# FPGA_14_15.net
KiCad netlist of a schematic drawn in Altium Designer
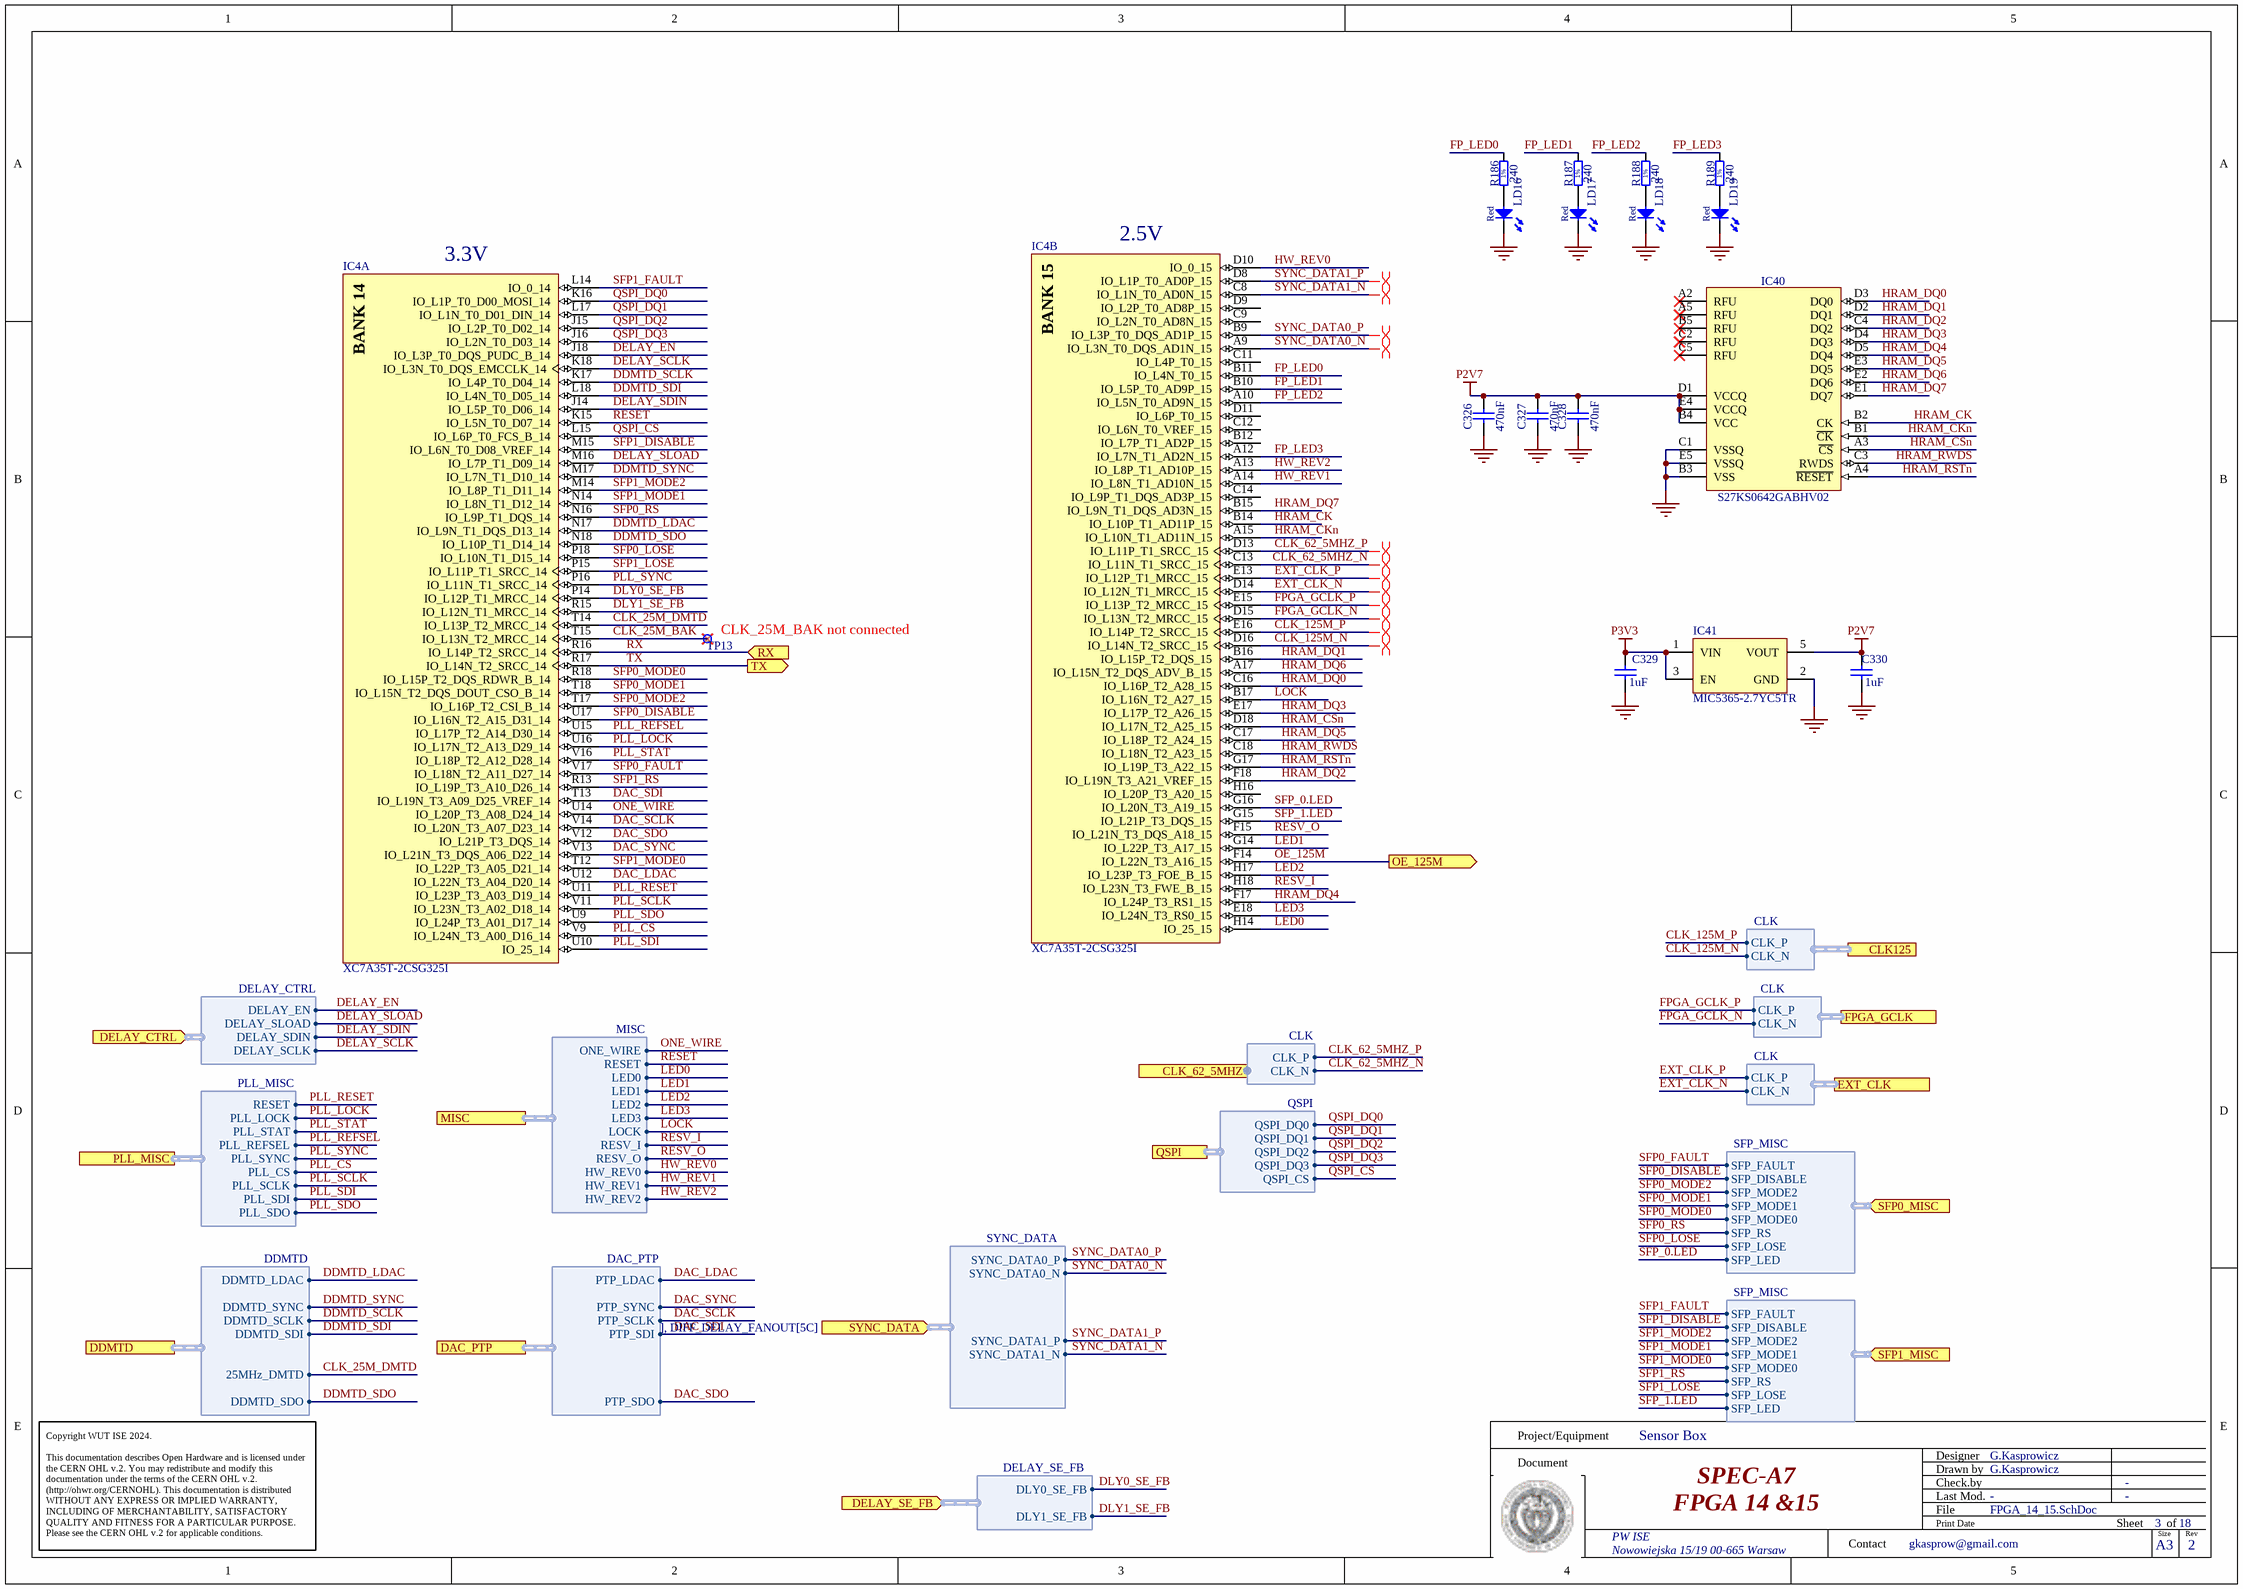
[diagram p0: FPGA_14_15.SchDoc]

(export (version "E")
  (design (tool "Eeschema 10.0.6"))
  (components
    (comp (ref "C326")
      (value "470nF")
      (footprint "CAPC0603X33N")
      (description "Non-polarised capacitor")
      (fields
        (field (name "PART NUMBER") "CC0201_470NF_4V_20%_X5R")
        (field (name "VOLTAGE") "4V")
        (field (name "AUTHOR") "CERN DEM JLC")
      )
      (libsource (lib "Capacitors") (part "Capacitor - non polarized"))
    )
    (comp (ref "C327")
      (value "470nF")
      (footprint "CAPC0603X33N")
      (description "Non-polarised capacitor")
      (fields
        (field (name "PART NUMBER") "CC0201_470NF_4V_20%_X5R")
        (field (name "VOLTAGE") "4V")
        (field (name "AUTHOR") "CERN DEM JLC")
      )
      (libsource (lib "Capacitors") (part "Capacitor - non polarized"))
    )
    (comp (ref "C328")
      (value "470nF")
      (footprint "CAPC0603X33N")
      (description "Non-polarised capacitor")
      (fields
        (field (name "PART NUMBER") "CC0201_470NF_4V_20%_X5R")
        (field (name "VOLTAGE") "4V")
        (field (name "AUTHOR") "CERN DEM JLC")
      )
      (libsource (lib "Capacitors") (part "Capacitor - non polarized"))
    )
    (comp (ref "C329")
      (value "1uF")
      (footprint "CAPC1005X55N")
      (description "Non-polarised capacitor")
      (fields
        (field (name "PART NUMBER") "CC0402_1UF_16V_10%_X5R")
        (field (name "VOLTAGE") "16V")
        (field (name "AUTHOR") "CERN DEM JLC")
      )
      (libsource (lib "Capacitors") (part "Capacitor - non polarized"))
    )
    (comp (ref "C330")
      (value "1uF")
      (footprint "CAPC1005X55N")
      (description "Non-polarised capacitor")
      (fields
        (field (name "PART NUMBER") "CC0402_1UF_16V_10%_X5R")
        (field (name "VOLTAGE") "16V")
        (field (name "AUTHOR") "CERN DEM JLC")
      )
      (libsource (lib "Capacitors") (part "Capacitor - non polarized"))
    )
    (comp (ref "IC4")
      (value "XC7A35T-2CSG325I")
      (footprint "CSG325")
      (description "Artix-7 FPGA, 150 User I/Os, 4 GTP, 324-Ball BGA, Speed Grade 2, Industrial Grade, Pb-Free")
      (fields (field (name "MANUFACTURER") "Xilinx"))
      (libsource (lib "Altium Content Vault") (part "XLNX-XC7A35T-CSG325"))
    )
    (comp (ref "IC40")
      (value "S27KS0642GABHV02")
      (footprint "BGA24C100P5X5_600X800X100")
      (description "1.8V, Multiple I/O Serial NOR Flash Memory, with Reset# & Hold# Pins")
      (fields (field (name "MANUFACTURER") "INFINEON") (field (name "AUTHOR") "CERN DEM HF"))
      (libsource (lib "ICs And Semiconductors") (part "S27KS0642GABHV02"))
    )
    (comp (ref "IC41")
      (value "MIC5365-2.7YC5TR")
      (footprint "SOT65P210X110-5N")
      (libsource (lib "MGlib") (part "MIC5365-2.7YC5TR"))
    )
    (comp (ref "LD16")
      (value "Red")
      (footprint "LED_AVAGO_HSMC-C120")
      (description "LED Red 1C 2A")
      (fields
        (field (name "PART NUMBER") "LED_AVAGO_HSMC-C120")
        (field (name "MANUFACTURER") "AVAGO TECHNOLOGIES")
        (field (name "AUTHOR") "CERN DEM JMW")
      )
      (libsource (lib "ICs And Semiconductors") (part "LED Red 1C 2A"))
    )
    (comp (ref "LD17")
      (value "Red")
      (footprint "LED_AVAGO_HSMC-C120")
      (description "LED Red 1C 2A")
      (fields
        (field (name "PART NUMBER") "LED_AVAGO_HSMC-C120")
        (field (name "MANUFACTURER") "AVAGO TECHNOLOGIES")
        (field (name "AUTHOR") "CERN DEM JMW")
      )
      (libsource (lib "ICs And Semiconductors") (part "LED Red 1C 2A"))
    )
    (comp (ref "LD18")
      (value "Red")
      (footprint "LED_AVAGO_HSMC-C120")
      (description "LED Red 1C 2A")
      (fields
        (field (name "PART NUMBER") "LED_AVAGO_HSMC-C120")
        (field (name "MANUFACTURER") "AVAGO TECHNOLOGIES")
        (field (name "AUTHOR") "CERN DEM JMW")
      )
      (libsource (lib "ICs And Semiconductors") (part "LED Red 1C 2A"))
    )
    (comp (ref "LD19")
      (value "Red")
      (footprint "LED_AVAGO_HSMC-C120")
      (description "LED Red 1C 2A")
      (fields
        (field (name "PART NUMBER") "LED_AVAGO_HSMC-C120")
        (field (name "MANUFACTURER") "AVAGO TECHNOLOGIES")
        (field (name "AUTHOR") "CERN DEM JMW")
      )
      (libsource (lib "ICs And Semiconductors") (part "LED Red 1C 2A"))
    )
    (comp (ref "R186")
      (value "240")
      (footprint "RESC1005X40N")
      (description "Resistor - 1%")
      (fields
        (field (name "PART NUMBER") "R0402_240R_1%_0.0625W_100PPM")
        (field (name "POWER") "0.0625W")
        (field (name "AUTHOR") "CERN DEM JLC")
      )
      (libsource (lib "Resistors") (part "Resistor - 1%"))
    )
    (comp (ref "R187")
      (value "240")
      (footprint "RESC1005X40N")
      (description "Resistor - 1%")
      (fields
        (field (name "PART NUMBER") "R0402_240R_1%_0.0625W_100PPM")
        (field (name "POWER") "0.0625W")
        (field (name "AUTHOR") "CERN DEM JLC")
      )
      (libsource (lib "Resistors") (part "Resistor - 1%"))
    )
    (comp (ref "R188")
      (value "240")
      (footprint "RESC1005X40N")
      (description "Resistor - 1%")
      (fields
        (field (name "PART NUMBER") "R0402_240R_1%_0.0625W_100PPM")
        (field (name "POWER") "0.0625W")
        (field (name "AUTHOR") "CERN DEM JLC")
      )
      (libsource (lib "Resistors") (part "Resistor - 1%"))
    )
    (comp (ref "R189")
      (value "240")
      (footprint "RESC1005X40N")
      (description "Resistor - 1%")
      (fields
        (field (name "PART NUMBER") "R0402_240R_1%_0.0625W_100PPM")
        (field (name "POWER") "0.0625W")
        (field (name "AUTHOR") "CERN DEM JLC")
      )
      (libsource (lib "Resistors") (part "Resistor - 1%"))
    )
    (comp (ref "TP13")
      (value "Test Point")
      (footprint "TPS060")
      (fields (field (name "PART NUMBER") "SMD_PAD_0.6X0.6MM") (field (name "AUTHOR") "CERN DEM HF"))
      (libsource (lib "Eletro-mechanical") (part "Test Point"))
    )
  )
  (nets
    (net (code "11") (name "/CLK_25M_BAK") (class "Default")
      (node (ref "IC4") (pin "T15") (pinfunction "IO_L13N_T2_MRCC_14_T15") (pintype "bidirectional"))
      (node (ref "TP13") (pin "1") (pinfunction "1_1") (pintype "bidirectional"))
    )
    (net (code "12") (name "/CLK_25M_DMTD") (class "Default")
      (node (ref "IC4") (pin "T14") (pinfunction "IO_L13P_T2_MRCC_14_T14") (pintype "bidirectional"))
    )
    (net (code "13") (name "/CLK_62_5MHZ_N") (class "Default")
      (node (ref "IC4") (pin "C13") (pinfunction "IO_L11N_T1_SRCC_15_C13") (pintype "bidirectional"))
    )
    (net (code "14") (name "/CLK_62_5MHZ_P") (class "Default")
      (node (ref "IC4") (pin "D13") (pinfunction "IO_L11P_T1_SRCC_15_D13") (pintype "bidirectional"))
    )
    (net (code "15") (name "/CLK_125M_N") (class "Default")
      (node (ref "IC4") (pin "D16") (pinfunction "IO_L14N_T2_SRCC_15_D16") (pintype "bidirectional"))
    )
    (net (code "16") (name "/CLK_125M_P") (class "Default")
      (node (ref "IC4") (pin "E16") (pinfunction "IO_L14P_T2_SRCC_15_E16") (pintype "bidirectional"))
    )
    (net (code "17") (name "/DAC_LDAC") (class "Default")
      (node (ref "IC4") (pin "U12") (pinfunction "IO_L22N_T3_A04_D20_14_U12") (pintype "bidirectional"))
    )
    (net (code "18") (name "/DAC_SCLK") (class "Default")
      (node (ref "IC4") (pin "V14") (pinfunction "IO_L20N_T3_A07_D23_14_V14") (pintype "bidirectional"))
    )
    (net (code "19") (name "/DAC_SDI") (class "Default")
      (node (ref "IC4") (pin "T13") (pinfunction "IO_L19N_T3_A09_D25_VREF_14_T13") (pintype "bidirectional"))
    )
    (net (code "20") (name "/DAC_SDO") (class "Default")
      (node (ref "IC4") (pin "V12") (pinfunction "IO_L21P_T3_DQS_14_V12") (pintype "bidirectional"))
    )
    (net (code "21") (name "/DAC_SYNC") (class "Default")
      (node (ref "IC4") (pin "V13") (pinfunction "IO_L21N_T3_DQS_A06_D22_14_V13") (pintype "bidirectional"))
    )
    (net (code "22") (name "/DDMTD_LDAC") (class "Default")
      (node (ref "IC4") (pin "N17") (pinfunction "IO_L9N_T1_DQS_D13_14_N17") (pintype "bidirectional"))
    )
    (net (code "23") (name "/DDMTD_SCLK") (class "Default")
      (node (ref "IC4") (pin "K17") (pinfunction "IO_L4P_T0_D04_14_K17") (pintype "bidirectional"))
    )
    (net (code "24") (name "/DDMTD_SDI") (class "Default")
      (node (ref "IC4") (pin "L18") (pinfunction "IO_L4N_T0_D05_14_L18") (pintype "bidirectional"))
    )
    (net (code "25") (name "/DDMTD_SDO") (class "Default")
      (node (ref "IC4") (pin "N18") (pinfunction "IO_L10P_T1_D14_14_N18") (pintype "bidirectional"))
    )
    (net (code "26") (name "/DDMTD_SYNC") (class "Default")
      (node (ref "IC4") (pin "M17") (pinfunction "IO_L7N_T1_D10_14_M17") (pintype "bidirectional"))
    )
    (net (code "27") (name "/DELAY_EN") (class "Default")
      (node (ref "IC4") (pin "J18") (pinfunction "IO_L3P_T0_DQS_PUDC_B_14_J18") (pintype "bidirectional"))
    )
    (net (code "28") (name "/DELAY_SCLK") (class "Default")
      (node (ref "IC4") (pin "K18") (pinfunction "IO_L3N_T0_DQS_EMCCLK_14_K18") (pintype "bidirectional"))
    )
    (net (code "29") (name "/DELAY_SDIN") (class "Default")
      (node (ref "IC4") (pin "J14") (pinfunction "IO_L5P_T0_D06_14_J14") (pintype "bidirectional"))
    )
    (net (code "30") (name "/DELAY_SLOAD") (class "Default")
      (node (ref "IC4") (pin "M16") (pinfunction "IO_L7P_T1_D09_14_M16") (pintype "bidirectional"))
    )
    (net (code "31") (name "/DLY0_SE_FB") (class "Default")
      (node (ref "IC4") (pin "P14") (pinfunction "IO_L12P_T1_MRCC_14_P14") (pintype "bidirectional"))
    )
    (net (code "32") (name "/DLY1_SE_FB") (class "Default")
      (node (ref "IC4") (pin "R15") (pinfunction "IO_L12N_T1_MRCC_14_R15") (pintype "bidirectional"))
    )
    (net (code "33") (name "/EXT_CLK_N") (class "Default")
      (node (ref "IC4") (pin "D14") (pinfunction "IO_L12N_T1_MRCC_15_D14") (pintype "bidirectional"))
    )
    (net (code "34") (name "/EXT_CLK_P") (class "Default")
      (node (ref "IC4") (pin "E13") (pinfunction "IO_L12P_T1_MRCC_15_E13") (pintype "bidirectional"))
    )
    (net (code "35") (name "/FPGA_GCLK_N") (class "Default")
      (node (ref "IC4") (pin "D15") (pinfunction "IO_L13N_T2_MRCC_15_D15") (pintype "bidirectional"))
    )
    (net (code "36") (name "/FPGA_GCLK_P") (class "Default")
      (node (ref "IC4") (pin "E15") (pinfunction "IO_L13P_T2_MRCC_15_E15") (pintype "bidirectional"))
    )
    (net (code "37") (name "/FP_LED0") (class "Default")
      (node (ref "IC4") (pin "B11") (pinfunction "IO_L4N_T0_15_B11") (pintype "bidirectional"))
      (node (ref "R186") (pin "2") (pinfunction "2_2") (pintype "passive"))
    )
    (net (code "38") (name "/FP_LED1") (class "Default")
      (node (ref "IC4") (pin "B10") (pinfunction "IO_L5P_T0_AD9P_15_B10") (pintype "bidirectional"))
      (node (ref "R187") (pin "2") (pinfunction "2_2") (pintype "passive"))
    )
    (net (code "39") (name "/FP_LED2") (class "Default")
      (node (ref "IC4") (pin "A10") (pinfunction "IO_L5N_T0_AD9N_15_A10") (pintype "bidirectional"))
      (node (ref "R188") (pin "2") (pinfunction "2_2") (pintype "passive"))
    )
    (net (code "40") (name "/FP_LED3") (class "Default")
      (node (ref "IC4") (pin "A12") (pinfunction "IO_L7N_T1_AD2N_15_A12") (pintype "bidirectional"))
      (node (ref "R189") (pin "2") (pinfunction "2_2") (pintype "passive"))
    )
    (net (code "41") (name "/HRAM_CK") (class "Default")
      (node (ref "IC4") (pin "B14") (pinfunction "IO_L10P_T1_AD11P_15_B14") (pintype "bidirectional"))
      (node (ref "IC40") (pin "B2") (pinfunction "CK_B2") (pintype "input"))
    )
    (net (code "42") (name "/HRAM_CKn") (class "Default")
      (node (ref "IC4") (pin "A15") (pinfunction "IO_L10N_T1_AD11N_15_A15") (pintype "bidirectional"))
      (node (ref "IC40") (pin "B1") (pinfunction "~{CK}_B1") (pintype "input"))
    )
    (net (code "43") (name "/HRAM_CSn") (class "Default")
      (node (ref "IC4") (pin "D18") (pinfunction "IO_L17N_T2_A25_15_D18") (pintype "bidirectional"))
      (node (ref "IC40") (pin "A3") (pinfunction "~{CS}_A3") (pintype "input"))
    )
    (net (code "44") (name "/HRAM_DQ0") (class "Default")
      (node (ref "IC4") (pin "C16") (pinfunction "IO_L16P_T2_A28_15_C16") (pintype "bidirectional"))
      (node (ref "IC40") (pin "D3") (pinfunction "DQ0_D3") (pintype "bidirectional"))
    )
    (net (code "45") (name "/HRAM_DQ1") (class "Default")
      (node (ref "IC4") (pin "B16") (pinfunction "IO_L15P_T2_DQS_15_B16") (pintype "bidirectional"))
      (node (ref "IC40") (pin "D2") (pinfunction "DQ1_D2") (pintype "bidirectional"))
    )
    (net (code "46") (name "/HRAM_DQ2") (class "Default")
      (node (ref "IC4") (pin "F18") (pinfunction "IO_L19N_T3_A21_VREF_15_F18") (pintype "bidirectional"))
      (node (ref "IC40") (pin "C4") (pinfunction "DQ2_C4") (pintype "bidirectional"))
    )
    (net (code "47") (name "/HRAM_DQ3") (class "Default")
      (node (ref "IC4") (pin "E17") (pinfunction "IO_L17P_T2_A26_15_E17") (pintype "bidirectional"))
      (node (ref "IC40") (pin "D4") (pinfunction "DQ3_D4") (pintype "bidirectional"))
    )
    (net (code "48") (name "/HRAM_DQ4") (class "Default")
      (node (ref "IC4") (pin "F17") (pinfunction "IO_L24P_T3_RS1_15_F17") (pintype "bidirectional"))
      (node (ref "IC40") (pin "D5") (pinfunction "DQ4_D5") (pintype "bidirectional"))
    )
    (net (code "49") (name "/HRAM_DQ5") (class "Default")
      (node (ref "IC4") (pin "C17") (pinfunction "IO_L18P_T2_A24_15_C17") (pintype "bidirectional"))
      (node (ref "IC40") (pin "E3") (pinfunction "DQ5_E3") (pintype "bidirectional"))
    )
    (net (code "50") (name "/HRAM_DQ6") (class "Default")
      (node (ref "IC4") (pin "A17") (pinfunction "IO_L15N_T2_DQS_ADV_B_15_A17") (pintype "bidirectional"))
      (node (ref "IC40") (pin "E2") (pinfunction "DQ6_E2") (pintype "bidirectional"))
    )
    (net (code "51") (name "/HRAM_DQ7") (class "Default")
      (node (ref "IC4") (pin "B15") (pinfunction "IO_L9N_T1_DQS_AD3N_15_B15") (pintype "bidirectional"))
      (node (ref "IC40") (pin "E1") (pinfunction "DQ7_E1") (pintype "bidirectional"))
    )
    (net (code "52") (name "/HRAM_RSTn") (class "Default")
      (node (ref "IC4") (pin "G17") (pinfunction "IO_L19P_T3_A22_15_G17") (pintype "bidirectional"))
      (node (ref "IC40") (pin "A4") (pinfunction "~{RESET}_A4") (pintype "input"))
    )
    (net (code "53") (name "/HRAM_RWDS") (class "Default")
      (node (ref "IC4") (pin "C18") (pinfunction "IO_L18N_T2_A23_15_C18") (pintype "bidirectional"))
      (node (ref "IC40") (pin "C3") (pinfunction "RWDS_C3") (pintype "bidirectional"))
    )
    (net (code "54") (name "/HW_REV0") (class "Default")
      (node (ref "IC4") (pin "D10") (pinfunction "IO_0_15_D10") (pintype "bidirectional"))
    )
    (net (code "55") (name "/HW_REV1") (class "Default")
      (node (ref "IC4") (pin "A14") (pinfunction "IO_L8N_T1_AD10N_15_A14") (pintype "bidirectional"))
    )
    (net (code "56") (name "/HW_REV2") (class "Default")
      (node (ref "IC4") (pin "A13") (pinfunction "IO_L8P_T1_AD10P_15_A13") (pintype "bidirectional"))
    )
    (net (code "57") (name "/LED0") (class "Default")
      (node (ref "IC4") (pin "H14") (pinfunction "IO_25_15_H14") (pintype "bidirectional"))
    )
    (net (code "58") (name "/LED1") (class "Default")
      (node (ref "IC4") (pin "G14") (pinfunction "IO_L22P_T3_A17_15_G14") (pintype "bidirectional"))
    )
    (net (code "59") (name "/LED2") (class "Default")
      (node (ref "IC4") (pin "H17") (pinfunction "IO_L23P_T3_FOE_B_15_H17") (pintype "bidirectional"))
    )
    (net (code "60") (name "/LED3") (class "Default")
      (node (ref "IC4") (pin "E18") (pinfunction "IO_L24N_T3_RS0_15_E18") (pintype "bidirectional"))
    )
    (net (code "61") (name "/LOCK") (class "Default")
      (node (ref "IC4") (pin "B17") (pinfunction "IO_L16N_T2_A27_15_B17") (pintype "bidirectional"))
    )
    (net (code "62") (name "/OE_125M") (class "Default")
      (node (ref "IC4") (pin "F14") (pinfunction "IO_L22N_T3_A16_15_F14") (pintype "bidirectional"))
    )
    (net (code "63") (name "/ONE_WIRE") (class "Default")
      (node (ref "IC4") (pin "U14") (pinfunction "IO_L20P_T3_A08_D24_14_U14") (pintype "bidirectional"))
    )
    (net (code "64") (name "/PLL_CS") (class "Default")
      (node (ref "IC4") (pin "V9") (pinfunction "IO_L24N_T3_A00_D16_14_V9") (pintype "bidirectional"))
    )
    (net (code "65") (name "/PLL_LOCK") (class "Default")
      (node (ref "IC4") (pin "U16") (pinfunction "IO_L17N_T2_A13_D29_14_U16") (pintype "bidirectional"))
    )
    (net (code "66") (name "/PLL_REFSEL") (class "Default")
      (node (ref "IC4") (pin "U15") (pinfunction "IO_L17P_T2_A14_D30_14_U15") (pintype "bidirectional"))
    )
    (net (code "67") (name "/PLL_RESET") (class "Default")
      (node (ref "IC4") (pin "U11") (pinfunction "IO_L23P_T3_A03_D19_14_U11") (pintype "bidirectional"))
    )
    (net (code "68") (name "/PLL_SCLK") (class "Default")
      (node (ref "IC4") (pin "V11") (pinfunction "IO_L23N_T3_A02_D18_14_V11") (pintype "bidirectional"))
    )
    (net (code "69") (name "/PLL_SDI") (class "Default")
      (node (ref "IC4") (pin "U10") (pinfunction "IO_25_14_U10") (pintype "bidirectional"))
    )
    (net (code "70") (name "/PLL_SDO") (class "Default")
      (node (ref "IC4") (pin "U9") (pinfunction "IO_L24P_T3_A01_D17_14_U9") (pintype "bidirectional"))
    )
    (net (code "71") (name "/PLL_STAT") (class "Default")
      (node (ref "IC4") (pin "V16") (pinfunction "IO_L18P_T2_A12_D28_14_V16") (pintype "bidirectional"))
    )
    (net (code "72") (name "/PLL_SYNC") (class "Default")
      (node (ref "IC4") (pin "P16") (pinfunction "IO_L11N_T1_SRCC_14_P16") (pintype "bidirectional"))
    )
    (net (code "73") (name "/QSPI_CS") (class "Default")
      (node (ref "IC4") (pin "L15") (pinfunction "IO_L6P_T0_FCS_B_14_L15") (pintype "bidirectional"))
    )
    (net (code "74") (name "/QSPI_DQ0") (class "Default")
      (node (ref "IC4") (pin "K16") (pinfunction "IO_L1P_T0_D00_MOSI_14_K16") (pintype "bidirectional"))
    )
    (net (code "75") (name "/QSPI_DQ1") (class "Default")
      (node (ref "IC4") (pin "L17") (pinfunction "IO_L1N_T0_D01_DIN_14_L17") (pintype "bidirectional"))
    )
    (net (code "76") (name "/QSPI_DQ2") (class "Default")
      (node (ref "IC4") (pin "J15") (pinfunction "IO_L2P_T0_D02_14_J15") (pintype "bidirectional"))
    )
    (net (code "77") (name "/QSPI_DQ3") (class "Default")
      (node (ref "IC4") (pin "J16") (pinfunction "IO_L2N_T0_D03_14_J16") (pintype "bidirectional"))
    )
    (net (code "78") (name "/RESET") (class "Default")
      (node (ref "IC4") (pin "K15") (pinfunction "IO_L5N_T0_D07_14_K15") (pintype "bidirectional"))
    )
    (net (code "79") (name "/RESV_I") (class "Default")
      (node (ref "IC4") (pin "H18") (pinfunction "IO_L23N_T3_FWE_B_15_H18") (pintype "bidirectional"))
    )
    (net (code "80") (name "/RESV_O") (class "Default")
      (node (ref "IC4") (pin "F15") (pinfunction "IO_L21N_T3_DQS_A18_15_F15") (pintype "bidirectional"))
    )
    (net (code "81") (name "/RX") (class "Default")
      (node (ref "IC4") (pin "R16") (pinfunction "IO_L14P_T2_SRCC_14_R16") (pintype "bidirectional"))
    )
    (net (code "82") (name "/SFP0_DISABLE") (class "Default")
      (node (ref "IC4") (pin "U17") (pinfunction "IO_L16N_T2_A15_D31_14_U17") (pintype "bidirectional"))
    )
    (net (code "83") (name "/SFP0_FAULT") (class "Default")
      (node (ref "IC4") (pin "V17") (pinfunction "IO_L18N_T2_A11_D27_14_V17") (pintype "bidirectional"))
    )
    (net (code "84") (name "/SFP0_LOSE") (class "Default")
      (node (ref "IC4") (pin "P18") (pinfunction "IO_L10N_T1_D15_14_P18") (pintype "bidirectional"))
    )
    (net (code "85") (name "/SFP0_MODE0") (class "Default")
      (node (ref "IC4") (pin "R18") (pinfunction "IO_L15P_T2_DQS_RDWR_B_14_R18") (pintype "bidirectional"))
    )
    (net (code "86") (name "/SFP0_MODE1") (class "Default")
      (node (ref "IC4") (pin "T18") (pinfunction "IO_L15N_T2_DQS_DOUT_CSO_B_14_T18") (pintype "bidirectional"))
    )
    (net (code "87") (name "/SFP0_MODE2") (class "Default")
      (node (ref "IC4") (pin "T17") (pinfunction "IO_L16P_T2_CSI_B_14_T17") (pintype "bidirectional"))
    )
    (net (code "88") (name "/SFP0_RS") (class "Default")
      (node (ref "IC4") (pin "N16") (pinfunction "IO_L9P_T1_DQS_14_N16") (pintype "bidirectional"))
    )
    (net (code "89") (name "/SFP1_DISABLE") (class "Default")
      (node (ref "IC4") (pin "M15") (pinfunction "IO_L6N_T0_D08_VREF_14_M15") (pintype "bidirectional"))
    )
    (net (code "90") (name "/SFP1_FAULT") (class "Default")
      (node (ref "IC4") (pin "L14") (pinfunction "IO_0_14_L14") (pintype "bidirectional"))
    )
    (net (code "91") (name "/SFP1_LOSE") (class "Default")
      (node (ref "IC4") (pin "P15") (pinfunction "IO_L11P_T1_SRCC_14_P15") (pintype "bidirectional"))
    )
    (net (code "92") (name "/SFP1_MODE0") (class "Default")
      (node (ref "IC4") (pin "T12") (pinfunction "IO_L22P_T3_A05_D21_14_T12") (pintype "bidirectional"))
    )
    (net (code "93") (name "/SFP1_MODE1") (class "Default")
      (node (ref "IC4") (pin "N14") (pinfunction "IO_L8N_T1_D12_14_N14") (pintype "bidirectional"))
    )
    (net (code "94") (name "/SFP1_MODE2") (class "Default")
      (node (ref "IC4") (pin "M14") (pinfunction "IO_L8P_T1_D11_14_M14") (pintype "bidirectional"))
    )
    (net (code "95") (name "/SFP1_RS") (class "Default")
      (node (ref "IC4") (pin "R13") (pinfunction "IO_L19P_T3_A10_D26_14_R13") (pintype "bidirectional"))
    )
    (net (code "96") (name "/SFP_0.LED") (class "Default")
      (node (ref "IC4") (pin "G16") (pinfunction "IO_L20N_T3_A19_15_G16") (pintype "bidirectional"))
    )
    (net (code "97") (name "/SFP_1.LED") (class "Default")
      (node (ref "IC4") (pin "G15") (pinfunction "IO_L21P_T3_DQS_15_G15") (pintype "bidirectional"))
    )
    (net (code "98") (name "/SYNC_DATA0_N") (class "Default")
      (node (ref "IC4") (pin "A9") (pinfunction "IO_L3N_T0_DQS_AD1N_15_A9") (pintype "bidirectional"))
    )
    (net (code "99") (name "/SYNC_DATA0_P") (class "Default")
      (node (ref "IC4") (pin "B9") (pinfunction "IO_L3P_T0_DQS_AD1P_15_B9") (pintype "bidirectional"))
    )
    (net (code "100") (name "/SYNC_DATA1_N") (class "Default")
      (node (ref "IC4") (pin "C8") (pinfunction "IO_L1N_T0_AD0N_15_C8") (pintype "bidirectional"))
    )
    (net (code "101") (name "/SYNC_DATA1_P") (class "Default")
      (node (ref "IC4") (pin "D8") (pinfunction "IO_L1P_T0_AD0P_15_D8") (pintype "bidirectional"))
    )
    (net (code "102") (name "/TX") (class "Default")
      (node (ref "IC4") (pin "R17") (pinfunction "IO_L14N_T2_SRCC_14_R17") (pintype "bidirectional"))
    )
    (net (code "113") (name "GND") (class "Default")
      (node (ref "C326") (pin "1") (pinfunction "1_1") (pintype "passive"))
      (node (ref "C327") (pin "1") (pinfunction "1_1") (pintype "passive"))
      (node (ref "C328") (pin "1") (pinfunction "1_1") (pintype "passive"))
      (node (ref "C329") (pin "1") (pinfunction "1_1") (pintype "passive"))
      (node (ref "C330") (pin "1") (pinfunction "1_1") (pintype "passive"))
      (node (ref "IC40") (pin "B3") (pinfunction "VSS_B3") (pintype "power_in"))
      (node (ref "IC40") (pin "C1") (pinfunction "VSSQ_C1") (pintype "power_in"))
      (node (ref "IC40") (pin "E5") (pinfunction "VSSQ_E5") (pintype "power_in"))
      (node (ref "IC41") (pin "2") (pinfunction "GND_2") (pintype "passive"))
      (node (ref "LD16") (pin "1") (pinfunction "C_1") (pintype "passive"))
      (node (ref "LD17") (pin "1") (pinfunction "C_1") (pintype "passive"))
      (node (ref "LD18") (pin "1") (pinfunction "C_1") (pintype "passive"))
      (node (ref "LD19") (pin "1") (pinfunction "C_1") (pintype "passive"))
    )
    (net (code "114") (name "Net-(LD16-A)") (class "Default")
      (node (ref "LD16") (pin "2") (pinfunction "A_2") (pintype "passive"))
      (node (ref "R186") (pin "1") (pinfunction "1_1") (pintype "passive"))
    )
    (net (code "115") (name "Net-(LD17-A)") (class "Default")
      (node (ref "LD17") (pin "2") (pinfunction "A_2") (pintype "passive"))
      (node (ref "R187") (pin "1") (pinfunction "1_1") (pintype "passive"))
    )
    (net (code "116") (name "Net-(LD18-A)") (class "Default")
      (node (ref "LD18") (pin "2") (pinfunction "A_2") (pintype "passive"))
      (node (ref "R188") (pin "1") (pinfunction "1_1") (pintype "passive"))
    )
    (net (code "117") (name "Net-(LD19-A)") (class "Default")
      (node (ref "LD19") (pin "2") (pinfunction "A_2") (pintype "passive"))
      (node (ref "R189") (pin "1") (pinfunction "1_1") (pintype "passive"))
    )
    (net (code "118") (name "P2V7") (class "Default")
      (node (ref "C326") (pin "2") (pinfunction "2_2") (pintype "passive"))
      (node (ref "C327") (pin "2") (pinfunction "2_2") (pintype "passive"))
      (node (ref "C328") (pin "2") (pinfunction "2_2") (pintype "passive"))
      (node (ref "C330") (pin "2") (pinfunction "2_2") (pintype "passive"))
      (node (ref "IC40") (pin "B4") (pinfunction "VCC_B4") (pintype "power_in"))
      (node (ref "IC40") (pin "D1") (pinfunction "VCCQ_D1") (pintype "power_in"))
      (node (ref "IC40") (pin "E4") (pinfunction "VCCQ_E4") (pintype "power_in"))
      (node (ref "IC41") (pin "5") (pinfunction "VOUT_5") (pintype "passive"))
    )
    (net (code "119") (name "P3V3") (class "Default")
      (node (ref "C329") (pin "2") (pinfunction "2_2") (pintype "passive"))
      (node (ref "IC41") (pin "1") (pinfunction "VIN_1") (pintype "passive"))
      (node (ref "IC41") (pin "3") (pinfunction "EN_3") (pintype "passive"))
    )
    (net (code "120") (name "unconnected-(IC4B-IO_L2N_T0_AD8N_15-PadC9)") (class "Default")
      (node (ref "IC4") (pin "C9") (pinfunction "IO_L2N_T0_AD8N_15_C9") (pintype "bidirectional"))
    )
    (net (code "121") (name "unconnected-(IC4B-IO_L2P_T0_AD8P_15-PadD9)") (class "Default")
      (node (ref "IC4") (pin "D9") (pinfunction "IO_L2P_T0_AD8P_15_D9") (pintype "bidirectional"))
    )
    (net (code "122") (name "unconnected-(IC4B-IO_L4P_T0_15-PadC11)") (class "Default")
      (node (ref "IC4") (pin "C11") (pinfunction "IO_L4P_T0_15_C11") (pintype "bidirectional"))
    )
    (net (code "123") (name "unconnected-(IC4B-IO_L6N_T0_VREF_15-PadC12)") (class "Default")
      (node (ref "IC4") (pin "C12") (pinfunction "IO_L6N_T0_VREF_15_C12") (pintype "bidirectional"))
    )
    (net (code "124") (name "unconnected-(IC4B-IO_L6P_T0_15-PadD11)") (class "Default")
      (node (ref "IC4") (pin "D11") (pinfunction "IO_L6P_T0_15_D11") (pintype "bidirectional"))
    )
    (net (code "125") (name "unconnected-(IC4B-IO_L7P_T1_AD2P_15-PadB12)") (class "Default")
      (node (ref "IC4") (pin "B12") (pinfunction "IO_L7P_T1_AD2P_15_B12") (pintype "bidirectional"))
    )
    (net (code "126") (name "unconnected-(IC4B-IO_L9P_T1_DQS_AD3P_15-PadC14)") (class "Default")
      (node (ref "IC4") (pin "C14") (pinfunction "IO_L9P_T1_DQS_AD3P_15_C14") (pintype "bidirectional"))
    )
    (net (code "127") (name "unconnected-(IC4B-IO_L20P_T3_A20_15-PadH16)") (class "Default")
      (node (ref "IC4") (pin "H16") (pinfunction "IO_L20P_T3_A20_15_H16") (pintype "bidirectional"))
    )
    (net (code "128") (name "unconnected-(IC40-RFU-PadA2)") (class "Default")
      (node (ref "IC40") (pin "A2") (pinfunction "RFU_A2") (pintype "passive+no_connect"))
    )
    (net (code "129") (name "unconnected-(IC40-RFU-PadA5)") (class "Default")
      (node (ref "IC40") (pin "A5") (pinfunction "RFU_A5") (pintype "passive+no_connect"))
    )
    (net (code "130") (name "unconnected-(IC40-RFU-PadB5)") (class "Default")
      (node (ref "IC40") (pin "B5") (pinfunction "RFU_B5") (pintype "passive+no_connect"))
    )
    (net (code "131") (name "unconnected-(IC40-RFU-PadC2)") (class "Default")
      (node (ref "IC40") (pin "C2") (pinfunction "RFU_C2") (pintype "passive+no_connect"))
    )
    (net (code "132") (name "unconnected-(IC40-RFU-PadC5)") (class "Default")
      (node (ref "IC40") (pin "C5") (pinfunction "RFU_C5") (pintype "passive+no_connect"))
    )
  )
)
